# STC12C5A60S2_Core.net
KiCad netlist of a schematic drawn in Altium Designer
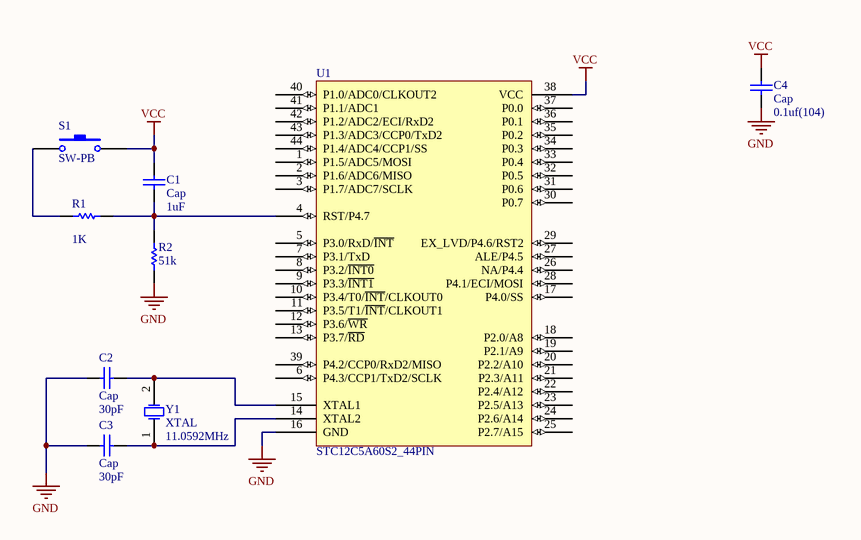
[diagram p0: STC12C5A60S2_Core.SchDoc]

(export (version "E")
  (design (tool "Eeschema 10.0.6"))
  (components
    (comp (ref "C1")
      (value "Cap")
      (footprint "C0805")
      (description "Non-Polar Capacitor")
      (fields (field (name "ALTIUM_VALUE") "1uF"))
      (libsource (lib "Integrated_Library") (part "Cap"))
    )
    (comp (ref "C2")
      (value "Cap")
      (footprint "C0805")
      (description "Non-Polar Capacitor")
      (fields (field (name "ALTIUM_VALUE") "30pF"))
      (libsource (lib "Integrated_Library") (part "Cap"))
    )
    (comp (ref "C3")
      (value "Cap")
      (footprint "C0805")
      (description "Non-Polar Capacitor")
      (fields (field (name "ALTIUM_VALUE") "30pF"))
      (libsource (lib "Integrated_Library") (part "Cap"))
    )
    (comp (ref "C4")
      (value "Cap")
      (footprint "C0805")
      (description "Non-Polar Capacitor")
      (fields (field (name "ALTIUM_VALUE") "0.1uf(104)"))
      (libsource (lib "Integrated_Library") (part "Cap"))
    )
    (comp (ref "R1")
      (value "1K")
      (footprint "R0805")
      (description "Resistor")
      (fields (field (name "Comment") "Res1"))
      (libsource (lib "Integrated_Library") (part "Res1"))
    )
    (comp (ref "R2")
      (value "51k")
      (footprint "R0805")
      (description "Resistor")
      (fields (field (name "Comment") "Res1"))
      (libsource (lib "Integrated_Library") (part "Res1"))
    )
    (comp (ref "S1")
      (value "SW-PB")
      (footprint "KEY-DIP4")
      (description "Switch")
      (libsource (lib "Schlib") (part "SW-PB"))
    )
    (comp (ref "U1")
      (value "STC12C5A60S2_44PIN")
      (footprint "STC12C5A60S2_44PIN")
      (libsource (lib "Integrated_Library") (part "STC12C5A60S2_44PIN"))
    )
    (comp (ref "Y1")
      (value "XTAL")
      (footprint "XTAL-HC49S-SMD")
      (description "Crystal Oscillator")
      (fields (field (name "OSCILLATIONFREQUENCY") "11.0592MHz"))
      (libsource (lib "Integrated_Library") (part "XTAL_1"))
    )
  )
  (nets
    (net (code "1") (name "GND") (class "Default")
      (node (ref "C2") (pin "1") (pinfunction "1_1") (pintype "passive"))
      (node (ref "C3") (pin "1") (pinfunction "1_1") (pintype "passive"))
      (node (ref "C4") (pin "1") (pinfunction "1_1") (pintype "passive"))
      (node (ref "R2") (pin "1") (pinfunction "1_1") (pintype "passive"))
      (node (ref "U1") (pin "16") (pinfunction "GND_16") (pintype "power_in"))
    )
    (net (code "2") (name "Net-(R1-Pad1)") (class "Default")
      (node (ref "R1") (pin "1") (pinfunction "1_1") (pintype "passive"))
      (node (ref "S1") (pin "1") (pinfunction "1_1") (pintype "passive"))
    )
    (net (code "3") (name "Net-(U1-RST{slash}P4.7)") (class "Default")
      (node (ref "C1") (pin "1") (pinfunction "1_1") (pintype "passive"))
      (node (ref "R1") (pin "2") (pinfunction "2_2") (pintype "passive"))
      (node (ref "R2") (pin "2") (pinfunction "2_2") (pintype "passive"))
      (node (ref "U1") (pin "4") (pinfunction "RST/P4.7_4") (pintype "bidirectional"))
    )
    (net (code "4") (name "Net-(U1-XTAL1)") (class "Default")
      (node (ref "C2") (pin "2") (pinfunction "2_2") (pintype "passive"))
      (node (ref "U1") (pin "15") (pinfunction "XTAL1_15") (pintype "passive"))
      (node (ref "Y1") (pin "2") (pinfunction "OSC2_2") (pintype "passive"))
    )
    (net (code "5") (name "Net-(U1-XTAL2)") (class "Default")
      (node (ref "C3") (pin "2") (pinfunction "2_2") (pintype "passive"))
      (node (ref "U1") (pin "14") (pinfunction "XTAL2_14") (pintype "passive"))
      (node (ref "Y1") (pin "1") (pinfunction "OSC1_1") (pintype "passive"))
    )
    (net (code "6") (name "VCC") (class "Default")
      (node (ref "C1") (pin "2") (pinfunction "2_2") (pintype "passive"))
      (node (ref "C4") (pin "2") (pinfunction "2_2") (pintype "passive"))
      (node (ref "S1") (pin "2") (pinfunction "2_2") (pintype "passive"))
      (node (ref "U1") (pin "38") (pinfunction "VCC_38") (pintype "power_in"))
    )
    (net (code "7") (name "unconnected-(U1-ALE{slash}P4.5-Pad27)") (class "Default")
      (node (ref "U1") (pin "27") (pinfunction "ALE/P4.5_27") (pintype "bidirectional"))
    )
    (net (code "8") (name "unconnected-(U1-EX_LVD{slash}P4.6{slash}RST2-Pad29)") (class "Default")
      (node (ref "U1") (pin "29") (pinfunction "EX_LVD/P4.6/RST2_29") (pintype "bidirectional"))
    )
    (net (code "9") (name "unconnected-(U1-NA{slash}P4.4-Pad26)") (class "Default")
      (node (ref "U1") (pin "26") (pinfunction "NA/P4.4_26") (pintype "bidirectional"))
    )
    (net (code "10") (name "unconnected-(U1-P0.0-Pad37)") (class "Default")
      (node (ref "U1") (pin "37") (pinfunction "P0.0_37") (pintype "bidirectional"))
    )
    (net (code "11") (name "unconnected-(U1-P0.1-Pad36)") (class "Default")
      (node (ref "U1") (pin "36") (pinfunction "P0.1_36") (pintype "bidirectional"))
    )
    (net (code "12") (name "unconnected-(U1-P0.2-Pad35)") (class "Default")
      (node (ref "U1") (pin "35") (pinfunction "P0.2_35") (pintype "bidirectional"))
    )
    (net (code "13") (name "unconnected-(U1-P0.3-Pad34)") (class "Default")
      (node (ref "U1") (pin "34") (pinfunction "P0.3_34") (pintype "bidirectional"))
    )
    (net (code "14") (name "unconnected-(U1-P0.4-Pad33)") (class "Default")
      (node (ref "U1") (pin "33") (pinfunction "P0.4_33") (pintype "bidirectional"))
    )
    (net (code "15") (name "unconnected-(U1-P0.5-Pad32)") (class "Default")
      (node (ref "U1") (pin "32") (pinfunction "P0.5_32") (pintype "bidirectional"))
    )
    (net (code "16") (name "unconnected-(U1-P0.6-Pad31)") (class "Default")
      (node (ref "U1") (pin "31") (pinfunction "P0.6_31") (pintype "bidirectional"))
    )
    (net (code "17") (name "unconnected-(U1-P0.7-Pad30)") (class "Default")
      (node (ref "U1") (pin "30") (pinfunction "P0.7_30") (pintype "bidirectional"))
    )
    (net (code "18") (name "unconnected-(U1-P1.0{slash}ADC0{slash}CLKOUT2-Pad40)") (class "Default")
      (node (ref "U1") (pin "40") (pinfunction "P1.0/ADC0/CLKOUT2_40") (pintype "bidirectional"))
    )
    (net (code "19") (name "unconnected-(U1-P1.1{slash}ADC1-Pad41)") (class "Default")
      (node (ref "U1") (pin "41") (pinfunction "P1.1/ADC1_41") (pintype "bidirectional"))
    )
    (net (code "20") (name "unconnected-(U1-P1.2{slash}ADC2{slash}ECI{slash}RxD2-Pad42)") (class "Default")
      (node (ref "U1") (pin "42") (pinfunction "P1.2/ADC2/ECI/RxD2_42") (pintype "bidirectional"))
    )
    (net (code "21") (name "unconnected-(U1-P1.3{slash}ADC3{slash}CCP0{slash}TxD2-Pad43)") (class "Default")
      (node (ref "U1") (pin "43") (pinfunction "P1.3/ADC3/CCP0/TxD2_43") (pintype "bidirectional"))
    )
    (net (code "22") (name "unconnected-(U1-P1.4{slash}ADC4{slash}CCP1{slash}SS-Pad44)") (class "Default")
      (node (ref "U1") (pin "44") (pinfunction "P1.4/ADC4/CCP1/SS_44") (pintype "bidirectional"))
    )
    (net (code "23") (name "unconnected-(U1-P1.5{slash}ADC5{slash}MOSI-Pad1)") (class "Default")
      (node (ref "U1") (pin "1") (pinfunction "P1.5/ADC5/MOSI_1") (pintype "bidirectional"))
    )
    (net (code "24") (name "unconnected-(U1-P1.6{slash}ADC6{slash}MISO-Pad2)") (class "Default")
      (node (ref "U1") (pin "2") (pinfunction "P1.6/ADC6/MISO_2") (pintype "bidirectional"))
    )
    (net (code "25") (name "unconnected-(U1-P1.7{slash}ADC7{slash}SCLK-Pad3)") (class "Default")
      (node (ref "U1") (pin "3") (pinfunction "P1.7/ADC7/SCLK_3") (pintype "bidirectional"))
    )
    (net (code "26") (name "unconnected-(U1-P2.0{slash}A8-Pad18)") (class "Default")
      (node (ref "U1") (pin "18") (pinfunction "P2.0/A8_18") (pintype "bidirectional"))
    )
    (net (code "27") (name "unconnected-(U1-P2.1{slash}A9-Pad19)") (class "Default")
      (node (ref "U1") (pin "19") (pinfunction "P2.1/A9_19") (pintype "bidirectional"))
    )
    (net (code "28") (name "unconnected-(U1-P2.2{slash}A10-Pad20)") (class "Default")
      (node (ref "U1") (pin "20") (pinfunction "P2.2/A10_20") (pintype "bidirectional"))
    )
    (net (code "29") (name "unconnected-(U1-P2.3{slash}A11-Pad21)") (class "Default")
      (node (ref "U1") (pin "21") (pinfunction "P2.3/A11_21") (pintype "bidirectional"))
    )
    (net (code "30") (name "unconnected-(U1-P2.4{slash}A12-Pad22)") (class "Default")
      (node (ref "U1") (pin "22") (pinfunction "P2.4/A12_22") (pintype "bidirectional"))
    )
    (net (code "31") (name "unconnected-(U1-P2.5{slash}A13-Pad23)") (class "Default")
      (node (ref "U1") (pin "23") (pinfunction "P2.5/A13_23") (pintype "bidirectional"))
    )
    (net (code "32") (name "unconnected-(U1-P2.6{slash}A14-Pad24)") (class "Default")
      (node (ref "U1") (pin "24") (pinfunction "P2.6/A14_24") (pintype "bidirectional"))
    )
    (net (code "33") (name "unconnected-(U1-P2.7{slash}A15-Pad25)") (class "Default")
      (node (ref "U1") (pin "25") (pinfunction "P2.7/A15_25") (pintype "bidirectional"))
    )
    (net (code "34") (name "unconnected-(U1-P3.0{slash}RxD{slash}~{INT}-Pad5)") (class "Default")
      (node (ref "U1") (pin "5") (pinfunction "P3.0/RxD/~{INT}_5") (pintype "bidirectional"))
    )
    (net (code "35") (name "unconnected-(U1-P3.1{slash}TxD-Pad7)") (class "Default")
      (node (ref "U1") (pin "7") (pinfunction "P3.1/TxD_7") (pintype "bidirectional"))
    )
    (net (code "36") (name "unconnected-(U1-P3.2{slash}~{INT0}-Pad8)") (class "Default")
      (node (ref "U1") (pin "8") (pinfunction "P3.2/~{INT0}_8") (pintype "bidirectional"))
    )
    (net (code "37") (name "unconnected-(U1-P3.3{slash}~{INT1}-Pad9)") (class "Default")
      (node (ref "U1") (pin "9") (pinfunction "P3.3/~{INT1}_9") (pintype "bidirectional"))
    )
    (net (code "38") (name "unconnected-(U1-P3.4{slash}T0{slash}~{INT}{slash}CLKOUT0-Pad10)") (class "Default")
      (node (ref "U1") (pin "10") (pinfunction "P3.4/T0/~{INT}/CLKOUT0_10") (pintype "bidirectional"))
    )
    (net (code "39") (name "unconnected-(U1-P3.5{slash}T1{slash}~{INT}{slash}CLKOUT1-Pad11)") (class "Default")
      (node (ref "U1") (pin "11") (pinfunction "P3.5/T1/~{INT}/CLKOUT1_11") (pintype "bidirectional"))
    )
    (net (code "40") (name "unconnected-(U1-P3.6{slash}~{WR}-Pad12)") (class "Default")
      (node (ref "U1") (pin "12") (pinfunction "P3.6/~{WR}_12") (pintype "bidirectional"))
    )
    (net (code "41") (name "unconnected-(U1-P3.7{slash}~{RD}-Pad13)") (class "Default")
      (node (ref "U1") (pin "13") (pinfunction "P3.7/~{RD}_13") (pintype "bidirectional"))
    )
    (net (code "42") (name "unconnected-(U1-P4.0{slash}SS-Pad17)") (class "Default")
      (node (ref "U1") (pin "17") (pinfunction "P4.0/SS_17") (pintype "bidirectional"))
    )
    (net (code "43") (name "unconnected-(U1-P4.1{slash}ECI{slash}MOSI-Pad28)") (class "Default")
      (node (ref "U1") (pin "28") (pinfunction "P4.1/ECI/MOSI_28") (pintype "bidirectional"))
    )
    (net (code "44") (name "unconnected-(U1-P4.2{slash}CCP0{slash}RxD2{slash}MISO-Pad39)") (class "Default")
      (node (ref "U1") (pin "39") (pinfunction "P4.2/CCP0/RxD2/MISO_39") (pintype "bidirectional"))
    )
    (net (code "45") (name "unconnected-(U1-P4.3{slash}CCP1{slash}TxD2{slash}SCLK-Pad6)") (class "Default")
      (node (ref "U1") (pin "6") (pinfunction "P4.3/CCP1/TxD2/SCLK_6") (pintype "bidirectional"))
    )
  )
)
